# EEPROM_block.net
KiCad netlist of a schematic drawn in Altium Designer
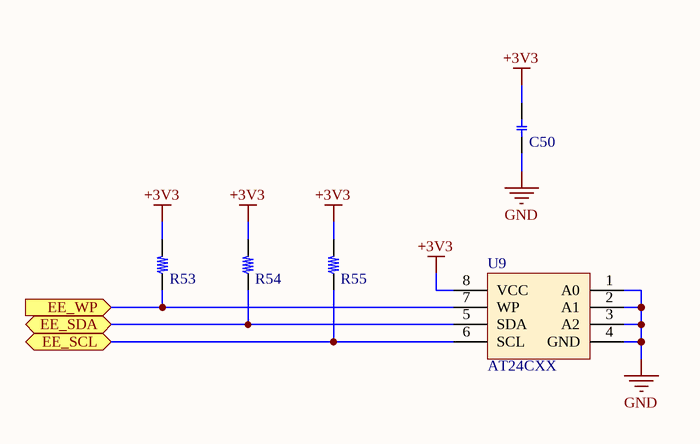
[diagram p0: EEPROM_block.SchDoc]

(export (version "E")
  (design (tool "Eeschema 10.0.6"))
  (components
    (comp (ref "C50")
      (value "CAP_SMD")
      (footprint "C 0603")
      (libsource (lib "radmehr_library") (part "CAP_SMD"))
    )
    (comp (ref "R53")
      (value "RES_SMD")
      (footprint "R 0603")
      (libsource (lib "radmehr_library") (part "RES_SMD"))
    )
    (comp (ref "R54")
      (value "RES_SMD")
      (footprint "R 0603")
      (libsource (lib "radmehr_library") (part "RES_SMD"))
    )
    (comp (ref "R55")
      (value "RES_SMD")
      (footprint "R 0603")
      (libsource (lib "radmehr_library") (part "RES_SMD"))
    )
    (comp (ref "U9")
      (value "AT24CXX")
      (footprint "SOIC-8")
      (libsource (lib "radmehr_library") (part "AT24CXX"))
    )
  )
  (nets
    (net (code "1") (name "+3V3") (class "Default")
      (node (ref "C50") (pin "2") (pinfunction "2_2") (pintype "passive"))
      (node (ref "R53") (pin "2") (pinfunction "2_2") (pintype "passive"))
      (node (ref "R54") (pin "2") (pinfunction "2_2") (pintype "passive"))
      (node (ref "R55") (pin "2") (pinfunction "2_2") (pintype "passive"))
      (node (ref "U9") (pin "8") (pinfunction "VCC_8") (pintype "passive"))
    )
    (net (code "2") (name "/EE_SCL") (class "Default")
      (node (ref "R55") (pin "1") (pinfunction "1_1") (pintype "passive"))
      (node (ref "U9") (pin "6") (pinfunction "SCL_6") (pintype "passive"))
    )
    (net (code "3") (name "/EE_SDA") (class "Default")
      (node (ref "R54") (pin "1") (pinfunction "1_1") (pintype "passive"))
      (node (ref "U9") (pin "5") (pinfunction "SDA_5") (pintype "passive"))
    )
    (net (code "4") (name "/EE_WP") (class "Default")
      (node (ref "R53") (pin "1") (pinfunction "1_1") (pintype "passive"))
      (node (ref "U9") (pin "7") (pinfunction "WP_7") (pintype "passive"))
    )
    (net (code "5") (name "GND") (class "Default")
      (node (ref "C50") (pin "1") (pinfunction "1_1") (pintype "passive"))
      (node (ref "U9") (pin "1") (pinfunction "A0_1") (pintype "passive"))
      (node (ref "U9") (pin "2") (pinfunction "A1_2") (pintype "passive"))
      (node (ref "U9") (pin "3") (pinfunction "A2_3") (pintype "passive"))
      (node (ref "U9") (pin "4") (pinfunction "GND_4") (pintype "passive"))
    )
  )
)
